# V_4.net
KiCad netlist of a schematic drawn in Altium Designer
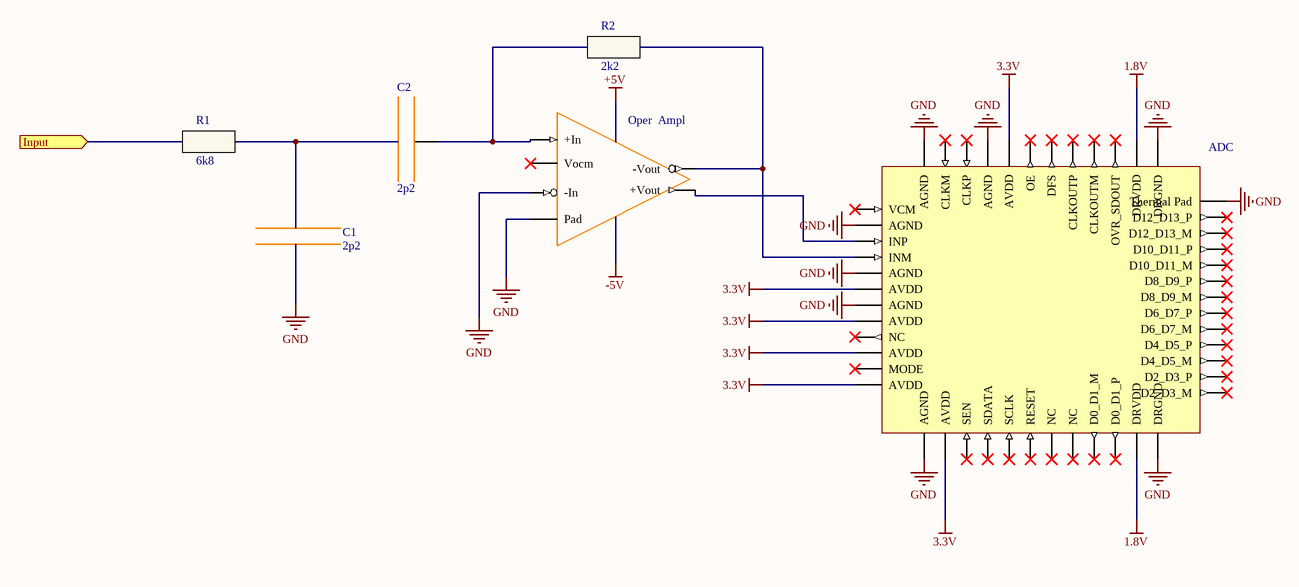
[diagram p0: V_4.SchDoc]

(export (version "E")
  (design (tool "Eeschema 10.0.6"))
  (components
    (comp (ref "C1") (value "2p2") (footprint "C_0805") (libsource (lib "V4") (part "Capasitor")))
    (comp (ref "C2") (value "2p2") (footprint "C_0805") (libsource (lib "V4") (part "Capasitor")))
    (comp (ref "R1") (value "6k8") (footprint "R_0805") (libsource (lib "V4") (part "Resistor")))
    (comp (ref "R2") (value "2k2") (footprint "R_0805") (libsource (lib "V4") (part "Resistor")))
    (comp (ref "U1") (value "Oper  Ampl") (footprint "ADA4932-1") (libsource (lib "V4") (part "Oper  Ampl")))
    (comp (ref "U2") (value "ADC") (footprint "ADS61b49") (libsource (lib "V4") (part "ADC")))
  )
  (nets
    (net (code "1") (name "+5V") (class "Default")
      (node (ref "U1") (pin "23") (pinfunction "+Vs_23") (pintype "passive"))
    )
    (net (code "2") (name "-5V") (class "Default")
      (node (ref "U1") (pin "22") (pinfunction "-Vs_22") (pintype "passive"))
    )
    (net (code "3") (name "/Input") (class "Default")
      (node (ref "R1") (pin "0") (pinfunction "0_0") (pintype "passive"))
    )
    (net (code "4") (name "1.8V") (class "Default")
      (node (ref "U2") (pin "27") (pinfunction "DRVDD_27") (pintype "power_in"))
      (node (ref "U2") (pin "60") (pinfunction "DRVDD_60") (pintype "power_in"))
    )
    (net (code "5") (name "3.3V") (class "Default")
      (node (ref "U2") (pin "33") (pinfunction "AVDD_33") (pintype "power_in"))
      (node (ref "U2") (pin "43") (pinfunction "AVDD_43") (pintype "power_in"))
      (node (ref "U2") (pin "45") (pinfunction "AVDD_45") (pintype "power_in"))
      (node (ref "U2") (pin "47") (pinfunction "AVDD_47") (pintype "power_in"))
      (node (ref "U2") (pin "49") (pinfunction "AVDD_49") (pintype "power_in"))
      (node (ref "U2") (pin "51") (pinfunction "AVDD_51") (pintype "power_in"))
    )
    (net (code "6") (name "GND") (class "Default")
      (node (ref "C1") (pin "3") (pinfunction "3_3") (pintype "passive"))
      (node (ref "U1") (pin "20") (pinfunction "-In_20") (pintype "input"))
      (node (ref "U1") (pin "21") (pinfunction "Pad_21") (pintype "passive"))
      (node (ref "U2") (pin "26") (pinfunction "DRGND_26") (pintype "power_in"))
      (node (ref "U2") (pin "34") (pinfunction "AGND_34") (pintype "power_in"))
      (node (ref "U2") (pin "37") (pinfunction "AGND_37") (pintype "power_in"))
      (node (ref "U2") (pin "39") (pinfunction "AGND_39") (pintype "power_in"))
      (node (ref "U2") (pin "42") (pinfunction "AGND_42") (pintype "power_in"))
      (node (ref "U2") (pin "44") (pinfunction "AGND_44") (pintype "power_in"))
      (node (ref "U2") (pin "50") (pinfunction "AGND_50") (pintype "power_in"))
      (node (ref "U2") (pin "61") (pinfunction "DRGND_61") (pintype "power_in"))
      (node (ref "U2") (pin "74") (pinfunction "Thermal_Pad_74") (pintype "power_in"))
    )
    (net (code "7") (name "Net-(C1-Pad2)") (class "Default")
      (node (ref "C1") (pin "2") (pinfunction "2_2") (pintype "passive"))
      (node (ref "C2") (pin "2") (pinfunction "2_2") (pintype "passive"))
      (node (ref "R1") (pin "1") (pinfunction "1_1") (pintype "passive"))
    )
    (net (code "8") (name "Net-(U1-+In)") (class "Default")
      (node (ref "R2") (pin "0") (pinfunction "0_0") (pintype "passive"))
      (node (ref "U1") (pin "18") (pinfunction "+In_18") (pintype "input"))
    )
    (net (code "9") (name "Net-(U1-+Vout)") (class "Default")
      (node (ref "U1") (pin "25") (pinfunction "+Vout_25") (pintype "output"))
      (node (ref "U2") (pin "40") (pinfunction "INP_40") (pintype "input"))
    )
    (net (code "10") (name "Net-(U1--Vout)") (class "Default")
      (node (ref "R2") (pin "1") (pinfunction "1_1") (pintype "passive"))
      (node (ref "U1") (pin "24") (pinfunction "-Vout_24") (pintype "output"))
      (node (ref "U2") (pin "41") (pinfunction "INM_41") (pintype "input"))
    )
    (net (code "11") (name "unconnected-(C2-Pad3)") (class "Default")
      (node (ref "C2") (pin "3") (pinfunction "3_3") (pintype "passive"))
    )
    (net (code "12") (name "unconnected-(U1-Vocm-Pad19)") (class "Default")
      (node (ref "U1") (pin "19") (pinfunction "Vocm_19") (pintype "passive+no_connect"))
    )
    (net (code "13") (name "unconnected-(U2-CLKM-Pad36)") (class "Default")
      (node (ref "U2") (pin "36") (pinfunction "CLKM_36") (pintype "input+no_connect"))
    )
    (net (code "14") (name "unconnected-(U2-CLKOUTM-Pad29)") (class "Default")
      (node (ref "U2") (pin "29") (pinfunction "CLKOUTM_29") (pintype "output+no_connect"))
    )
    (net (code "15") (name "unconnected-(U2-CLKOUTP-Pad30)") (class "Default")
      (node (ref "U2") (pin "30") (pinfunction "CLKOUTP_30") (pintype "output+no_connect"))
    )
    (net (code "16") (name "unconnected-(U2-CLKP-Pad35)") (class "Default")
      (node (ref "U2") (pin "35") (pinfunction "CLKP_35") (pintype "input+no_connect"))
    )
    (net (code "17") (name "unconnected-(U2-D0_D1_M-Pad58)") (class "Default")
      (node (ref "U2") (pin "58") (pinfunction "D0_D1_M_58") (pintype "output+no_connect"))
    )
    (net (code "18") (name "unconnected-(U2-D0_D1_P-Pad59)") (class "Default")
      (node (ref "U2") (pin "59") (pinfunction "D0_D1_P_59") (pintype "output+no_connect"))
    )
    (net (code "19") (name "unconnected-(U2-D2_D3_M-Pad62)") (class "Default")
      (node (ref "U2") (pin "62") (pinfunction "D2_D3_M_62") (pintype "output+no_connect"))
    )
    (net (code "20") (name "unconnected-(U2-D2_D3_P-Pad63)") (class "Default")
      (node (ref "U2") (pin "63") (pinfunction "D2_D3_P_63") (pintype "output+no_connect"))
    )
    (net (code "21") (name "unconnected-(U2-D4_D5_M-Pad64)") (class "Default")
      (node (ref "U2") (pin "64") (pinfunction "D4_D5_M_64") (pintype "output+no_connect"))
    )
    (net (code "22") (name "unconnected-(U2-D4_D5_P-Pad65)") (class "Default")
      (node (ref "U2") (pin "65") (pinfunction "D4_D5_P_65") (pintype "output+no_connect"))
    )
    (net (code "23") (name "unconnected-(U2-D6_D7_M-Pad66)") (class "Default")
      (node (ref "U2") (pin "66") (pinfunction "D6_D7_M_66") (pintype "output+no_connect"))
    )
    (net (code "24") (name "unconnected-(U2-D6_D7_P-Pad67)") (class "Default")
      (node (ref "U2") (pin "67") (pinfunction "D6_D7_P_67") (pintype "output+no_connect"))
    )
    (net (code "25") (name "unconnected-(U2-D8_D9_M-Pad68)") (class "Default")
      (node (ref "U2") (pin "68") (pinfunction "D8_D9_M_68") (pintype "output+no_connect"))
    )
    (net (code "26") (name "unconnected-(U2-D8_D9_P-Pad69)") (class "Default")
      (node (ref "U2") (pin "69") (pinfunction "D8_D9_P_69") (pintype "output+no_connect"))
    )
    (net (code "27") (name "unconnected-(U2-D10_D11_M-Pad70)") (class "Default")
      (node (ref "U2") (pin "70") (pinfunction "D10_D11_M_70") (pintype "output+no_connect"))
    )
    (net (code "28") (name "unconnected-(U2-D10_D11_P-Pad71)") (class "Default")
      (node (ref "U2") (pin "71") (pinfunction "D10_D11_P_71") (pintype "output+no_connect"))
    )
    (net (code "29") (name "unconnected-(U2-D12_D13_M-Pad72)") (class "Default")
      (node (ref "U2") (pin "72") (pinfunction "D12_D13_M_72") (pintype "output+no_connect"))
    )
    (net (code "30") (name "unconnected-(U2-D12_D13_P-Pad73)") (class "Default")
      (node (ref "U2") (pin "73") (pinfunction "D12_D13_P_73") (pintype "output+no_connect"))
    )
    (net (code "31") (name "unconnected-(U2-DFS-Pad31)") (class "Default")
      (node (ref "U2") (pin "31") (pinfunction "DFS_31") (pintype "output+no_connect"))
    )
    (net (code "32") (name "unconnected-(U2-MODE-Pad48)") (class "Default")
      (node (ref "U2") (pin "48") (pinfunction "MODE_48") (pintype "power_in+no_connect"))
    )
    (net (code "33") (name "unconnected-(U2-NC-Pad46)") (class "Default")
      (node (ref "U2") (pin "46") (pinfunction "NC_46") (pintype "output+no_connect"))
    )
    (net (code "34") (name "unconnected-(U2-NC-Pad56)") (class "Default")
      (node (ref "U2") (pin "56") (pinfunction "NC_56") (pintype "power_in+no_connect"))
    )
    (net (code "35") (name "unconnected-(U2-NC-Pad57)") (class "Default")
      (node (ref "U2") (pin "57") (pinfunction "NC_57") (pintype "power_in+no_connect"))
    )
    (net (code "36") (name "unconnected-(U2-OE-Pad32)") (class "Default")
      (node (ref "U2") (pin "32") (pinfunction "OE_32") (pintype "output+no_connect"))
    )
    (net (code "37") (name "unconnected-(U2-OVR_SDOUT-Pad28)") (class "Default")
      (node (ref "U2") (pin "28") (pinfunction "OVR_SDOUT_28") (pintype "output+no_connect"))
    )
    (net (code "38") (name "unconnected-(U2-RESET-Pad55)") (class "Default")
      (node (ref "U2") (pin "55") (pinfunction "RESET_55") (pintype "input+no_connect"))
    )
    (net (code "39") (name "unconnected-(U2-SCLK-Pad54)") (class "Default")
      (node (ref "U2") (pin "54") (pinfunction "SCLK_54") (pintype "input+no_connect"))
    )
    (net (code "40") (name "unconnected-(U2-SDATA-Pad53)") (class "Default")
      (node (ref "U2") (pin "53") (pinfunction "SDATA_53") (pintype "input+no_connect"))
    )
    (net (code "41") (name "unconnected-(U2-SEN-Pad52)") (class "Default")
      (node (ref "U2") (pin "52") (pinfunction "SEN_52") (pintype "input+no_connect"))
    )
    (net (code "42") (name "unconnected-(U2-VCM-Pad38)") (class "Default")
      (node (ref "U2") (pin "38") (pinfunction "VCM_38") (pintype "input+no_connect"))
    )
  )
)
